# Clock_Distribution.net
KiCad netlist of a schematic drawn in Altium Designer
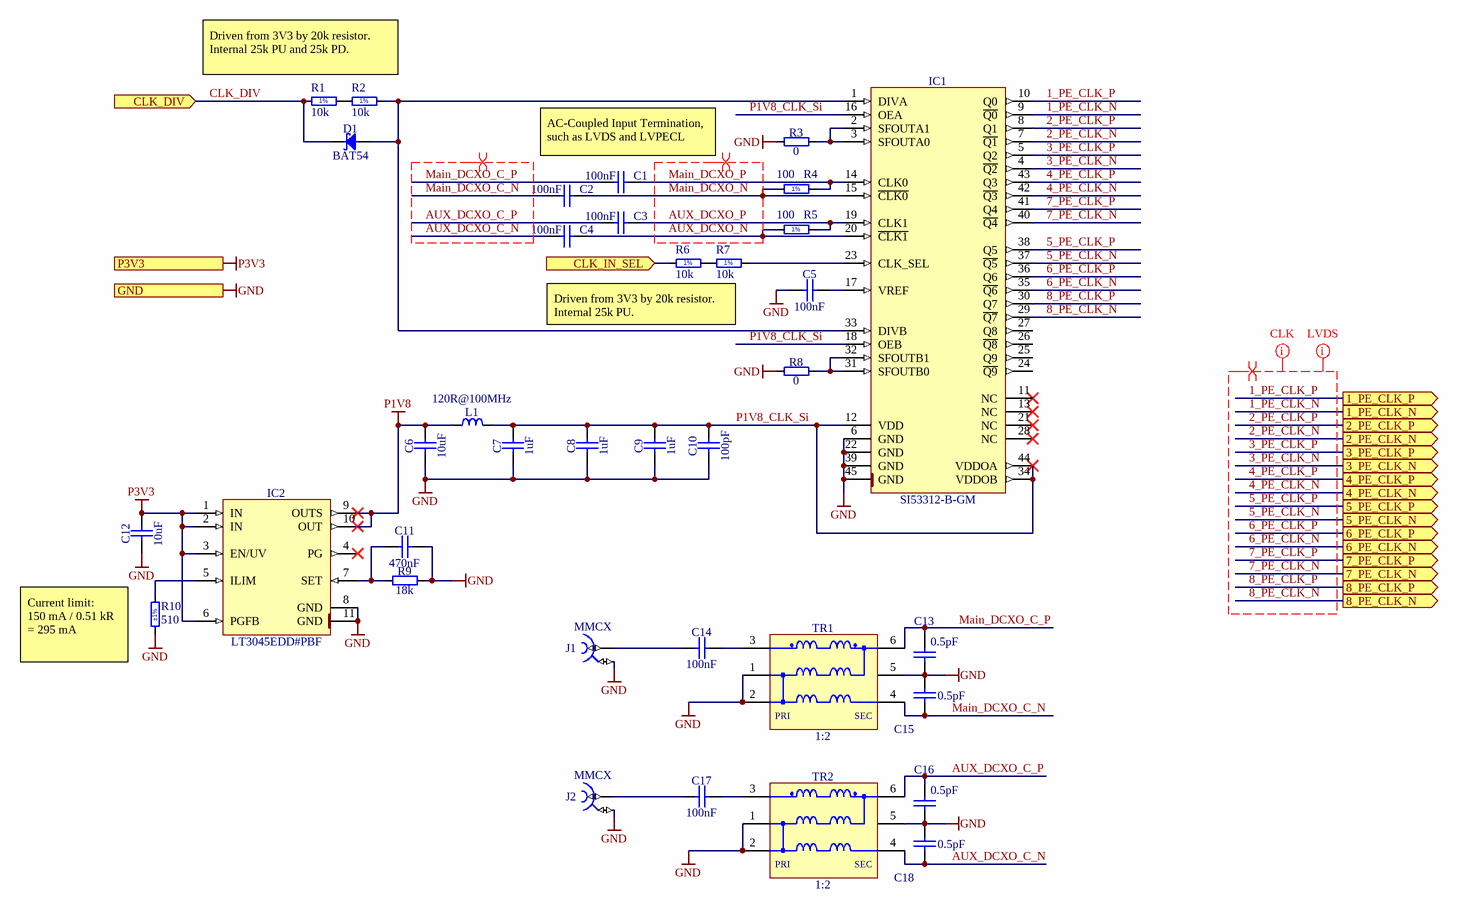
[diagram p0: Clock_Distribution.SchDoc]

(export (version "E")
  (design (tool "Eeschema 10.0.6"))
  (components
    (comp (ref "C1")
      (value "100nF")
      (footprint "CAPC0603X33N")
      (description "Non-polarised capacitor")
      (fields
        (field (name "PART NUMBER") "CC0201_100NF_6.3V_10%_X5R")
        (field (name "VOLTAGE") "6.3V")
        (field (name "AUTHOR") "CERN DEM JLC")
      )
      (libsource (lib "Capacitors") (part "Capacitor - non polarized"))
    )
    (comp (ref "C2")
      (value "100nF")
      (footprint "CAPC0603X33N")
      (description "Non-polarised capacitor")
      (fields
        (field (name "PART NUMBER") "CC0201_100NF_6.3V_10%_X5R")
        (field (name "VOLTAGE") "6.3V")
        (field (name "AUTHOR") "CERN DEM JLC")
      )
      (libsource (lib "Capacitors") (part "Capacitor - non polarized"))
    )
    (comp (ref "C3")
      (value "100nF")
      (footprint "CAPC0603X33N")
      (description "Non-polarised capacitor")
      (fields
        (field (name "PART NUMBER") "CC0201_100NF_6.3V_10%_X5R")
        (field (name "VOLTAGE") "6.3V")
        (field (name "AUTHOR") "CERN DEM JLC")
      )
      (libsource (lib "Capacitors") (part "Capacitor - non polarized"))
    )
    (comp (ref "C4")
      (value "100nF")
      (footprint "CAPC0603X33N")
      (description "Non-polarised capacitor")
      (fields
        (field (name "PART NUMBER") "CC0201_100NF_6.3V_10%_X5R")
        (field (name "VOLTAGE") "6.3V")
        (field (name "AUTHOR") "CERN DEM JLC")
      )
      (libsource (lib "Capacitors") (part "Capacitor - non polarized"))
    )
    (comp (ref "C5")
      (value "100nF")
      (footprint "CAPC1005X55N")
      (description "Non-polarised capacitor")
      (fields
        (field (name "PART NUMBER") "CC0402_100NF_16V_10%_X7R")
        (field (name "VOLTAGE") "16V")
        (field (name "AUTHOR") "CERN DEM JLC")
      )
      (libsource (lib "Capacitors") (part "Capacitor - non polarized"))
    )
    (comp (ref "C6")
      (value "10uF")
      (footprint "CAPC1608X80N")
      (description "Non-polarised capacitor")
      (fields
        (field (name "PART NUMBER") "CC0603_10UF_10V_10%_X5R")
        (field (name "VOLTAGE") "10V")
        (field (name "AUTHOR") "CERN DEM JLC")
      )
      (libsource (lib "Capacitors") (part "Capacitor - non polarized"))
    )
    (comp (ref "C7")
      (value "1uF")
      (footprint "CAPC1608X87N")
      (description "Non-polarised capacitor")
      (fields
        (field (name "PART NUMBER") "CC0603_1UF_25V_10%_X7R")
        (field (name "VOLTAGE") "25V")
        (field (name "AUTHOR") "CERN DEM JLC")
      )
      (libsource (lib "Capacitors") (part "Capacitor - non polarized"))
    )
    (comp (ref "C8")
      (value "1uF")
      (footprint "CAPC1608X87N")
      (description "Non-polarised capacitor")
      (fields
        (field (name "PART NUMBER") "CC0603_1UF_25V_10%_X7R")
        (field (name "VOLTAGE") "25V")
        (field (name "AUTHOR") "CERN DEM JLC")
      )
      (libsource (lib "Capacitors") (part "Capacitor - non polarized"))
    )
    (comp (ref "C9")
      (value "1uF")
      (footprint "CAPC1608X87N")
      (description "Non-polarised capacitor")
      (fields
        (field (name "PART NUMBER") "CC0603_1UF_25V_10%_X7R")
        (field (name "VOLTAGE") "25V")
        (field (name "AUTHOR") "CERN DEM JLC")
      )
      (libsource (lib "Capacitors") (part "Capacitor - non polarized"))
    )
    (comp (ref "C10")
      (value "100pF")
      (footprint "CAPC1005X55N")
      (description "Non-polarised capacitor")
      (fields
        (field (name "PART NUMBER") "CC0402_100PF_50V_5%_C0G")
        (field (name "VOLTAGE") "50V")
        (field (name "AUTHOR") "CERN DEM JLC")
      )
      (libsource (lib "Capacitors") (part "Capacitor - non polarized"))
    )
    (comp (ref "C11")
      (value "470nF")
      (footprint "CAPC1005X55N")
      (description "Non-polarised capacitor")
      (fields
        (field (name "PART NUMBER") "CC0402_470NF_16V_10%_X5R")
        (field (name "VOLTAGE") "16V")
        (field (name "AUTHOR") "CERN DEM JLC")
      )
      (libsource (lib "Capacitors") (part "Capacitor - non polarized"))
    )
    (comp (ref "C12")
      (value "10uF")
      (footprint "CAPC1608X80N")
      (description "Non-polarised capacitor")
      (fields
        (field (name "PART NUMBER") "CC0603_10UF_10V_10%_X5R")
        (field (name "VOLTAGE") "10V")
        (field (name "AUTHOR") "CERN DEM JLC")
      )
      (libsource (lib "Capacitors") (part "Capacitor - non polarized"))
    )
    (comp (ref "C13")
      (value "0.5pF")
      (footprint "CAPC1005X50N")
      (description "Non-polarised capacitor")
      (fields
        (field (name "PART NUMBER") "CC0402_0.5PF_25V_0.05PF_AVX_04023J0R5ABSTR")
        (field (name "VOLTAGE") "25V")
        (field (name "AUTHOR") "CERN DEM JLC")
      )
      (libsource (lib "Capacitors") (part "Capacitor - non polarized"))
    )
    (comp (ref "C14")
      (value "100nF")
      (footprint "CAPC1005X55N")
      (description "Non-polarised capacitor")
      (fields
        (field (name "PART NUMBER") "CC0402_100NF_16V_10%_X7R")
        (field (name "VOLTAGE") "16V")
        (field (name "AUTHOR") "CERN DEM JLC")
      )
      (libsource (lib "Capacitors") (part "Capacitor - non polarized"))
    )
    (comp (ref "C15")
      (value "0.5pF")
      (footprint "CAPC1005X50N")
      (description "Non-polarised capacitor")
      (fields
        (field (name "PART NUMBER") "CC0402_0.5PF_25V_0.05PF_AVX_04023J0R5ABSTR")
        (field (name "VOLTAGE") "25V")
        (field (name "AUTHOR") "CERN DEM JLC")
      )
      (libsource (lib "Capacitors") (part "Capacitor - non polarized"))
    )
    (comp (ref "C16")
      (value "0.5pF")
      (footprint "CAPC1005X50N")
      (description "Non-polarised capacitor")
      (fields
        (field (name "PART NUMBER") "CC0402_0.5PF_25V_0.05PF_AVX_04023J0R5ABSTR")
        (field (name "VOLTAGE") "25V")
        (field (name "AUTHOR") "CERN DEM JLC")
      )
      (libsource (lib "Capacitors") (part "Capacitor - non polarized"))
    )
    (comp (ref "C17")
      (value "100nF")
      (footprint "CAPC1005X55N")
      (description "Non-polarised capacitor")
      (fields
        (field (name "PART NUMBER") "CC0402_100NF_16V_10%_X7R")
        (field (name "VOLTAGE") "16V")
        (field (name "AUTHOR") "CERN DEM JLC")
      )
      (libsource (lib "Capacitors") (part "Capacitor - non polarized"))
    )
    (comp (ref "C18")
      (value "0.5pF")
      (footprint "CAPC1005X50N")
      (description "Non-polarised capacitor")
      (fields
        (field (name "PART NUMBER") "CC0402_0.5PF_25V_0.05PF_AVX_04023J0R5ABSTR")
        (field (name "VOLTAGE") "25V")
        (field (name "AUTHOR") "CERN DEM JLC")
      )
      (libsource (lib "Capacitors") (part "Capacitor - non polarized"))
    )
    (comp (ref "D1")
      (value "BAT54")
      (footprint "SOT95P240X130-3N")
      (description "Diode Schottky  Anode Pin 1 Cathode Pin 3 (Pas de pin 2)")
      (fields
        (field (name "VOLTAGE") "30V")
        (field (name "POWER") "200mA")
        (field (name "AUTHOR") "CERN DEM JLC")
      )
      (libsource (lib "ICs And Semiconductors") (part "Diode Schottky A1C3"))
    )
    (comp (ref "IC1")
      (value "SI53312-B-GM")
      (footprint "QFN50P700X700X90-45N-S295")
      (description "2 Input/10 Output, Low Jitter Universal Buffer/Level Translator With 2:1 Input Mux (<1.25 GHZ)")
      (fields (field (name "MANUFACTURER") "SILICON LABS") (field (name "AUTHOR") "CERN DEM MR"))
      (libsource (lib "ICs And Semiconductors") (part "SI53312"))
    )
    (comp (ref "IC2")
      (value "LT3045EDD#PBF")
      (footprint "SON50P300X300X80-11N-R175X248")
      (description "20V, 500mA, Ultralow Noise, Ultrahigh PSRR Linear Regulator")
      (fields (field (name "MANUFACTURER") "LINEAR TECHNOLOGY") (field (name "AUTHOR") "CERN DEM JLC"))
      (libsource (lib "ICs And Semiconductors") (part "LT3045EDD"))
    )
    (comp (ref "J1")
      (value "Coax_1Female_1Shield")
      (footprint "HUBER-SUHNER_85_MMCX-50-0-1/111_OE")
      (fields
        (field (name "PART NUMBER") "HUBER-SUHNER_85_MMCX-50-0-1/111_OE")
        (field (name "FAMILY") "MMCX")
        (field (name "MANUFACTURER") "HUBER+SUHNER")
        (field (name "MANUFACTURER PART NUMBER") "85_MMCX-50-0-1/111_OE")
        (field (name "AUTHOR") "CERN DEM JLC")
      )
      (libsource (lib "Connectors") (part "Coax_1Female_1Shield"))
    )
    (comp (ref "J2")
      (value "Coax_1Female_1Shield")
      (footprint "HUBER-SUHNER_85_MMCX-50-0-1/111_OE")
      (fields
        (field (name "PART NUMBER") "HUBER-SUHNER_85_MMCX-50-0-1/111_OE")
        (field (name "FAMILY") "MMCX")
        (field (name "MANUFACTURER") "HUBER+SUHNER")
        (field (name "MANUFACTURER PART NUMBER") "85_MMCX-50-0-1/111_OE")
        (field (name "AUTHOR") "CERN DEM JLC")
      )
      (libsource (lib "Connectors") (part "Coax_1Female_1Shield"))
    )
    (comp (ref "L1")
      (value "120R@100MHz")
      (footprint "INDC1608X95N")
      (description "Inductor")
      (fields
        (field (name "PART NUMBER") "IND0603_MURATA_BLM18PG121SN1D")
        (field (name "POWER") "2A")
        (field (name "AUTHOR") "CERN DEM BC")
      )
      (libsource (lib "Inductors & Transformers") (part "Inductor"))
    )
    (comp (ref "R1")
      (value "10k")
      (footprint "RESC1005X40N")
      (description "Resistor - 1%")
      (fields
        (field (name "PART NUMBER") "R0402_10K_1%_0.0625W_100PPM")
        (field (name "POWER") "0.0625W")
        (field (name "AUTHOR") "CERN DEM JLC")
      )
      (libsource (lib "Resistors") (part "Resistor - 1%"))
    )
    (comp (ref "R2")
      (value "10k")
      (footprint "RESC1005X40N")
      (description "Resistor - 1%")
      (fields
        (field (name "PART NUMBER") "R0402_10K_1%_0.0625W_100PPM")
        (field (name "POWER") "0.0625W")
        (field (name "AUTHOR") "CERN DEM JLC")
      )
      (libsource (lib "Resistors") (part "Resistor - 1%"))
    )
    (comp (ref "R3")
      (value "0")
      (footprint "RESC0603X28N")
      (description "Resistor")
      (fields
        (field (name "PART NUMBER") "R0201_0R_JUMPER")
        (field (name "MANUFACTURER") "GENERIC")
        (field (name "AUTHOR") "CERN DEM JLC")
      )
      (libsource (lib "Resistors") (part "Resistor"))
    )
    (comp (ref "R4")
      (value "100")
      (footprint "RESC1005X40N")
      (description "Resistor - 1%")
      (fields
        (field (name "PART NUMBER") "R0402_100R_1%_0.0625W_100PPM")
        (field (name "POWER") "0.0625W")
        (field (name "AUTHOR") "CERN DEM JLC")
      )
      (libsource (lib "Resistors") (part "Resistor - 1%"))
    )
    (comp (ref "R5")
      (value "100")
      (footprint "RESC1005X40N")
      (description "Resistor - 1%")
      (fields
        (field (name "PART NUMBER") "R0402_100R_1%_0.0625W_100PPM")
        (field (name "POWER") "0.0625W")
        (field (name "AUTHOR") "CERN DEM JLC")
      )
      (libsource (lib "Resistors") (part "Resistor - 1%"))
    )
    (comp (ref "R6")
      (value "10k")
      (footprint "RESC1005X40N")
      (description "Resistor - 1%")
      (fields
        (field (name "PART NUMBER") "R0402_10K_1%_0.0625W_100PPM")
        (field (name "POWER") "0.0625W")
        (field (name "AUTHOR") "CERN DEM JLC")
      )
      (libsource (lib "Resistors") (part "Resistor - 1%"))
    )
    (comp (ref "R7")
      (value "10k")
      (footprint "RESC1005X40N")
      (description "Resistor - 1%")
      (fields
        (field (name "PART NUMBER") "R0402_10K_1%_0.0625W_100PPM")
        (field (name "POWER") "0.0625W")
        (field (name "AUTHOR") "CERN DEM JLC")
      )
      (libsource (lib "Resistors") (part "Resistor - 1%"))
    )
    (comp (ref "R8")
      (value "0")
      (footprint "RESC0603X28N")
      (description "Resistor")
      (fields
        (field (name "PART NUMBER") "R0201_0R_JUMPER")
        (field (name "MANUFACTURER") "GENERIC")
        (field (name "AUTHOR") "CERN DEM JLC")
      )
      (libsource (lib "Resistors") (part "Resistor"))
    )
    (comp (ref "R9")
      (value "18k")
      (footprint "RESC1005X40N")
      (description "Resistor - 1%")
      (fields
        (field (name "PART NUMBER") "R0402_18K_1%_0.0625W_100PPM")
        (field (name "POWER") "0.0625W")
        (field (name "AUTHOR") "CERN DEM JLC")
      )
      (libsource (lib "Resistors") (part "Resistor - 1%"))
    )
    (comp (ref "R10")
      (value "510")
      (footprint "RESC1005X40N")
      (description "Resistor - 1%")
      (fields
        (field (name "TOLERANCE") "±1%")
        (field (name "PART NUMBER") "R0402_510R_1%_0.0625W_100PPM")
        (field (name "POWER") "0.0625W")
        (field (name "AUTHOR") "CERN DEM JLC")
      )
      (libsource (lib "Resistors") (part "Resistor - 1%"))
    )
    (comp (ref "TR1")
      (value "1:2")
      (footprint "XFMR_MINI-CIRCUITS_DB1627")
      (description "50 OHMS 10 to 4000 MHz RF Transformer")
      (fields
        (field (name "PART NUMBER") "XFMR_MINI-CIRCUITS_TCM2-43X+")
        (field (name "POWER") "0.4W")
        (field (name "AUTHOR") "CERN DEM BC")
      )
      (libsource (lib "Inductors & Transformers") (part "XFMR_MINI-CIRCUITS_TCM2-43X"))
    )
    (comp (ref "TR2")
      (value "1:2")
      (footprint "XFMR_MINI-CIRCUITS_DB1627")
      (description "50 OHMS 10 to 4000 MHz RF Transformer")
      (fields
        (field (name "PART NUMBER") "XFMR_MINI-CIRCUITS_TCM2-43X+")
        (field (name "POWER") "0.4W")
        (field (name "AUTHOR") "CERN DEM BC")
      )
      (libsource (lib "Inductors & Transformers") (part "XFMR_MINI-CIRCUITS_TCM2-43X"))
    )
  )
  (nets
    (net (code "1") (name "/1_PE_CLK_N") (class "Default")
      (node (ref "IC1") (pin "9") (pinfunction "~{Q0}_9") (pintype "output"))
    )
    (net (code "2") (name "/1_PE_CLK_P") (class "Default")
      (node (ref "IC1") (pin "10") (pinfunction "Q0_10") (pintype "output"))
    )
    (net (code "3") (name "/2_PE_CLK_N") (class "Default")
      (node (ref "IC1") (pin "7") (pinfunction "~{Q1}_7") (pintype "output"))
    )
    (net (code "4") (name "/2_PE_CLK_P") (class "Default")
      (node (ref "IC1") (pin "8") (pinfunction "Q1_8") (pintype "output"))
    )
    (net (code "5") (name "/3_PE_CLK_N") (class "Default")
      (node (ref "IC1") (pin "4") (pinfunction "~{Q2}_4") (pintype "output"))
    )
    (net (code "6") (name "/3_PE_CLK_P") (class "Default")
      (node (ref "IC1") (pin "5") (pinfunction "Q2_5") (pintype "output"))
    )
    (net (code "7") (name "/4_PE_CLK_N") (class "Default")
      (node (ref "IC1") (pin "42") (pinfunction "~{Q3}_42") (pintype "output"))
    )
    (net (code "8") (name "/4_PE_CLK_P") (class "Default")
      (node (ref "IC1") (pin "43") (pinfunction "Q3_43") (pintype "output"))
    )
    (net (code "9") (name "/5_PE_CLK_N") (class "Default")
      (node (ref "IC1") (pin "37") (pinfunction "~{Q5}_37") (pintype "output"))
    )
    (net (code "10") (name "/5_PE_CLK_P") (class "Default")
      (node (ref "IC1") (pin "38") (pinfunction "Q5_38") (pintype "output"))
    )
    (net (code "11") (name "/6_PE_CLK_N") (class "Default")
      (node (ref "IC1") (pin "35") (pinfunction "~{Q6}_35") (pintype "output"))
    )
    (net (code "12") (name "/6_PE_CLK_P") (class "Default")
      (node (ref "IC1") (pin "36") (pinfunction "Q6_36") (pintype "output"))
    )
    (net (code "13") (name "/7_PE_CLK_N") (class "Default")
      (node (ref "IC1") (pin "40") (pinfunction "~{Q4}_40") (pintype "output"))
    )
    (net (code "14") (name "/7_PE_CLK_P") (class "Default")
      (node (ref "IC1") (pin "41") (pinfunction "Q4_41") (pintype "output"))
    )
    (net (code "15") (name "/8_PE_CLK_N") (class "Default")
      (node (ref "IC1") (pin "29") (pinfunction "~{Q7}_29") (pintype "output"))
    )
    (net (code "16") (name "/8_PE_CLK_P") (class "Default")
      (node (ref "IC1") (pin "30") (pinfunction "Q7_30") (pintype "output"))
    )
    (net (code "17") (name "/AUX_DCXO_C_N") (class "Default")
      (node (ref "C18") (pin "1") (pinfunction "1_1") (pintype "passive"))
      (node (ref "C4") (pin "1") (pinfunction "1_1") (pintype "passive"))
      (node (ref "TR2") (pin "4") (pinfunction "S1_4") (pintype "passive"))
    )
    (net (code "18") (name "/AUX_DCXO_C_P") (class "Default")
      (node (ref "C16") (pin "2") (pinfunction "2_2") (pintype "passive"))
      (node (ref "C3") (pin "1") (pinfunction "1_1") (pintype "passive"))
      (node (ref "TR2") (pin "6") (pinfunction "S1_6") (pintype "passive"))
    )
    (net (code "19") (name "/AUX_DCXO_N") (class "Default")
      (node (ref "C4") (pin "2") (pinfunction "2_2") (pintype "passive"))
      (node (ref "IC1") (pin "20") (pinfunction "~{CLK1}_20") (pintype "input"))
      (node (ref "R5") (pin "1") (pinfunction "1_1") (pintype "passive"))
    )
    (net (code "20") (name "/AUX_DCXO_P") (class "Default")
      (node (ref "C3") (pin "2") (pinfunction "2_2") (pintype "passive"))
      (node (ref "IC1") (pin "19") (pinfunction "CLK1_19") (pintype "input"))
      (node (ref "R5") (pin "2") (pinfunction "2_2") (pintype "passive"))
    )
    (net (code "21") (name "/CLK_DIV") (class "Default")
      (node (ref "D1") (pin "3") (pinfunction "C_3") (pintype "passive"))
      (node (ref "R1") (pin "1") (pinfunction "1_1") (pintype "passive"))
    )
    (net (code "22") (name "/CLK_IN_SEL") (class "Default")
      (node (ref "R6") (pin "1") (pinfunction "1_1") (pintype "passive"))
    )
    (net (code "23") (name "/Main_DCXO_C_N") (class "Default")
      (node (ref "C15") (pin "1") (pinfunction "1_1") (pintype "passive"))
      (node (ref "C2") (pin "1") (pinfunction "1_1") (pintype "passive"))
      (node (ref "TR1") (pin "4") (pinfunction "S1_4") (pintype "passive"))
    )
    (net (code "24") (name "/Main_DCXO_C_P") (class "Default")
      (node (ref "C1") (pin "1") (pinfunction "1_1") (pintype "passive"))
      (node (ref "C13") (pin "2") (pinfunction "2_2") (pintype "passive"))
      (node (ref "TR1") (pin "6") (pinfunction "S1_6") (pintype "passive"))
    )
    (net (code "25") (name "/Main_DCXO_N") (class "Default")
      (node (ref "C2") (pin "2") (pinfunction "2_2") (pintype "passive"))
      (node (ref "IC1") (pin "15") (pinfunction "~{CLK0}_15") (pintype "input"))
      (node (ref "R4") (pin "1") (pinfunction "1_1") (pintype "passive"))
    )
    (net (code "26") (name "/Main_DCXO_P") (class "Default")
      (node (ref "C1") (pin "2") (pinfunction "2_2") (pintype "passive"))
      (node (ref "IC1") (pin "14") (pinfunction "CLK0_14") (pintype "input"))
      (node (ref "R4") (pin "2") (pinfunction "2_2") (pintype "passive"))
    )
    (net (code "27") (name "/P1V8_CLK_Si") (class "Default")
      (node (ref "C10") (pin "2") (pinfunction "2_2") (pintype "passive"))
      (node (ref "C7") (pin "2") (pinfunction "2_2") (pintype "passive"))
      (node (ref "C8") (pin "2") (pinfunction "2_2") (pintype "passive"))
      (node (ref "C9") (pin "2") (pinfunction "2_2") (pintype "passive"))
      (node (ref "IC1") (pin "12") (pinfunction "VDD_12") (pintype "power_in"))
      (node (ref "IC1") (pin "16") (pinfunction "OEA_16") (pintype "input"))
      (node (ref "IC1") (pin "18") (pinfunction "OEB_18") (pintype "input"))
      (node (ref "IC1") (pin "34") (pinfunction "VDDOB_34") (pintype "output"))
      (node (ref "IC1") (pin "44") (pinfunction "VDDOA_44") (pintype "output"))
      (node (ref "L1") (pin "1") (pinfunction "1_1") (pintype "passive"))
    )
    (net (code "28") (name "GND") (class "Default")
      (node (ref "C10") (pin "1") (pinfunction "1_1") (pintype "passive"))
      (node (ref "C11") (pin "2") (pinfunction "2_2") (pintype "passive"))
      (node (ref "C12") (pin "1") (pinfunction "1_1") (pintype "passive"))
      (node (ref "C13") (pin "1") (pinfunction "1_1") (pintype "passive"))
      (node (ref "C15") (pin "2") (pinfunction "2_2") (pintype "passive"))
      (node (ref "C16") (pin "1") (pinfunction "1_1") (pintype "passive"))
      (node (ref "C18") (pin "2") (pinfunction "2_2") (pintype "passive"))
      (node (ref "C5") (pin "1") (pinfunction "1_1") (pintype "passive"))
      (node (ref "C6") (pin "1") (pinfunction "1_1") (pintype "passive"))
      (node (ref "C7") (pin "1") (pinfunction "1_1") (pintype "passive"))
      (node (ref "C8") (pin "1") (pinfunction "1_1") (pintype "passive"))
      (node (ref "C9") (pin "1") (pinfunction "1_1") (pintype "passive"))
      (node (ref "IC1") (pin "22") (pinfunction "GND_22") (pintype "power_in"))
      (node (ref "IC1") (pin "39") (pinfunction "GND_39") (pintype "power_in"))
      (node (ref "IC1") (pin "45") (pinfunction "GND_45") (pintype "power_in"))
      (node (ref "IC1") (pin "6") (pinfunction "GND_6") (pintype "power_in"))
      (node (ref "IC2") (pin "11") (pinfunction "GND_11") (pintype "power_in"))
      (node (ref "IC2") (pin "8") (pinfunction "GND_8") (pintype "power_in"))
      (node (ref "J1") (pin "2") (pinfunction "2_2") (pintype "bidirectional"))
      (node (ref "J2") (pin "2") (pinfunction "2_2") (pintype "bidirectional"))
      (node (ref "R10") (pin "1") (pinfunction "1_1") (pintype "passive"))
      (node (ref "R3") (pin "1") (pinfunction "1_1") (pintype "passive"))
      (node (ref "R8") (pin "1") (pinfunction "1_1") (pintype "passive"))
      (node (ref "R9") (pin "2") (pinfunction "2_2") (pintype "passive"))
      (node (ref "TR1") (pin "1") (pinfunction "P1_1") (pintype "passive"))
      (node (ref "TR1") (pin "2") (pinfunction "P1_2") (pintype "passive"))
      (node (ref "TR1") (pin "5") (pinfunction "NC_5") (pintype "passive"))
      (node (ref "TR2") (pin "1") (pinfunction "P1_1") (pintype "passive"))
      (node (ref "TR2") (pin "2") (pinfunction "P1_2") (pintype "passive"))
      (node (ref "TR2") (pin "5") (pinfunction "NC_5") (pintype "passive"))
    )
    (net (code "29") (name "Net-(C14-Pad1)") (class "Default")
      (node (ref "C14") (pin "1") (pinfunction "1_1") (pintype "passive"))
      (node (ref "J1") (pin "1") (pinfunction "1_1") (pintype "bidirectional"))
    )
    (net (code "30") (name "Net-(C14-Pad2)") (class "Default")
      (node (ref "C14") (pin "2") (pinfunction "2_2") (pintype "passive"))
      (node (ref "TR1") (pin "3") (pinfunction "P1_3") (pintype "passive"))
    )
    (net (code "31") (name "Net-(C17-Pad1)") (class "Default")
      (node (ref "C17") (pin "1") (pinfunction "1_1") (pintype "passive"))
      (node (ref "J2") (pin "1") (pinfunction "1_1") (pintype "bidirectional"))
    )
    (net (code "32") (name "Net-(C17-Pad2)") (class "Default")
      (node (ref "C17") (pin "2") (pinfunction "2_2") (pintype "passive"))
      (node (ref "TR2") (pin "3") (pinfunction "P1_3") (pintype "passive"))
    )
    (net (code "33") (name "Net-(D1-A)") (class "Default")
      (node (ref "D1") (pin "1") (pinfunction "A_1") (pintype "passive"))
      (node (ref "IC1") (pin "1") (pinfunction "DIVA_1") (pintype "input"))
      (node (ref "IC1") (pin "33") (pinfunction "DIVB_33") (pintype "input"))
      (node (ref "R2") (pin "2") (pinfunction "2_2") (pintype "passive"))
    )
    (net (code "34") (name "Net-(IC1-CLK_SEL)") (class "Default")
      (node (ref "IC1") (pin "23") (pinfunction "CLK_SEL_23") (pintype "input"))
      (node (ref "R7") (pin "2") (pinfunction "2_2") (pintype "passive"))
    )
    (net (code "35") (name "Net-(IC1-SFOUTA0)") (class "Default")
      (node (ref "IC1") (pin "2") (pinfunction "SFOUTA1_2") (pintype "input"))
      (node (ref "IC1") (pin "3") (pinfunction "SFOUTA0_3") (pintype "input"))
      (node (ref "R3") (pin "2") (pinfunction "2_2") (pintype "passive"))
    )
    (net (code "36") (name "Net-(IC1-SFOUTB0)") (class "Default")
      (node (ref "IC1") (pin "31") (pinfunction "SFOUTB0_31") (pintype "input"))
      (node (ref "IC1") (pin "32") (pinfunction "SFOUTB1_32") (pintype "input"))
      (node (ref "R8") (pin "2") (pinfunction "2_2") (pintype "passive"))
    )
    (net (code "37") (name "Net-(IC1-VREF)") (class "Default")
      (node (ref "C5") (pin "2") (pinfunction "2_2") (pintype "passive"))
      (node (ref "IC1") (pin "17") (pinfunction "VREF_17") (pintype "input"))
    )
    (net (code "38") (name "Net-(IC2-ILIM)") (class "Default")
      (node (ref "IC2") (pin "5") (pinfunction "ILIM_5") (pintype "input"))
      (node (ref "R10") (pin "2") (pinfunction "2_2") (pintype "passive"))
    )
    (net (code "39") (name "Net-(IC2-SET)") (class "Default")
      (node (ref "C11") (pin "1") (pinfunction "1_1") (pintype "passive"))
      (node (ref "IC2") (pin "7") (pinfunction "SET_7") (pintype "input"))
      (node (ref "R9") (pin "1") (pinfunction "1_1") (pintype "passive"))
    )
    (net (code "40") (name "Net-(R1-Pad2)") (class "Default")
      (node (ref "R1") (pin "2") (pinfunction "2_2") (pintype "passive"))
      (node (ref "R2") (pin "1") (pinfunction "1_1") (pintype "passive"))
    )
    (net (code "41") (name "Net-(R6-Pad2)") (class "Default")
      (node (ref "R6") (pin "2") (pinfunction "2_2") (pintype "passive"))
      (node (ref "R7") (pin "1") (pinfunction "1_1") (pintype "passive"))
    )
    (net (code "42") (name "P1V8") (class "Default")
      (node (ref "C6") (pin "2") (pinfunction "2_2") (pintype "passive"))
      (node (ref "IC2") (pin "10") (pinfunction "OUT_10") (pintype "output"))
      (node (ref "IC2") (pin "9") (pinfunction "OUTS_9") (pintype "output"))
      (node (ref "L1") (pin "2") (pinfunction "2_2") (pintype "passive"))
    )
    (net (code "43") (name "P3V3") (class "Default")
      (node (ref "C12") (pin "2") (pinfunction "2_2") (pintype "passive"))
      (node (ref "IC2") (pin "1") (pinfunction "IN_1") (pintype "input"))
      (node (ref "IC2") (pin "2") (pinfunction "IN_2") (pintype "input"))
      (node (ref "IC2") (pin "3") (pinfunction "EN/UV_3") (pintype "input"))
      (node (ref "IC2") (pin "6") (pinfunction "PGFB_6") (pintype "input"))
    )
    (net (code "44") (name "unconnected-(IC1-NC-Pad11)") (class "Default")
      (node (ref "IC1") (pin "11") (pinfunction "NC_11") (pintype "passive+no_connect"))
    )
    (net (code "45") (name "unconnected-(IC1-NC-Pad13)") (class "Default")
      (node (ref "IC1") (pin "13") (pinfunction "NC_13") (pintype "passive+no_connect"))
    )
    (net (code "46") (name "unconnected-(IC1-NC-Pad21)") (class "Default")
      (node (ref "IC1") (pin "21") (pinfunction "NC_21") (pintype "passive+no_connect"))
    )
    (net (code "47") (name "unconnected-(IC1-NC-Pad28)") (class "Default")
      (node (ref "IC1") (pin "28") (pinfunction "NC_28") (pintype "passive+no_connect"))
    )
    (net (code "48") (name "unconnected-(IC1-Q8-Pad27)") (class "Default")
      (node (ref "IC1") (pin "27") (pinfunction "Q8_27") (pintype "output"))
    )
    (net (code "49") (name "unconnected-(IC1-Q9-Pad25)") (class "Default")
      (node (ref "IC1") (pin "25") (pinfunction "Q9_25") (pintype "output"))
    )
    (net (code "50") (name "unconnected-(IC1-~{Q8}-Pad26)") (class "Default")
      (node (ref "IC1") (pin "26") (pinfunction "~{Q8}_26") (pintype "output"))
    )
    (net (code "51") (name "unconnected-(IC1-~{Q9}-Pad24)") (class "Default")
      (node (ref "IC1") (pin "24") (pinfunction "~{Q9}_24") (pintype "output"))
    )
    (net (code "52") (name "unconnected-(IC2-PG-Pad4)") (class "Default")
      (node (ref "IC2") (pin "4") (pinfunction "PG_4") (pintype "output+no_connect"))
    )
  )
)
